# light.net
KiCad netlist of a schematic drawn in EAGLE
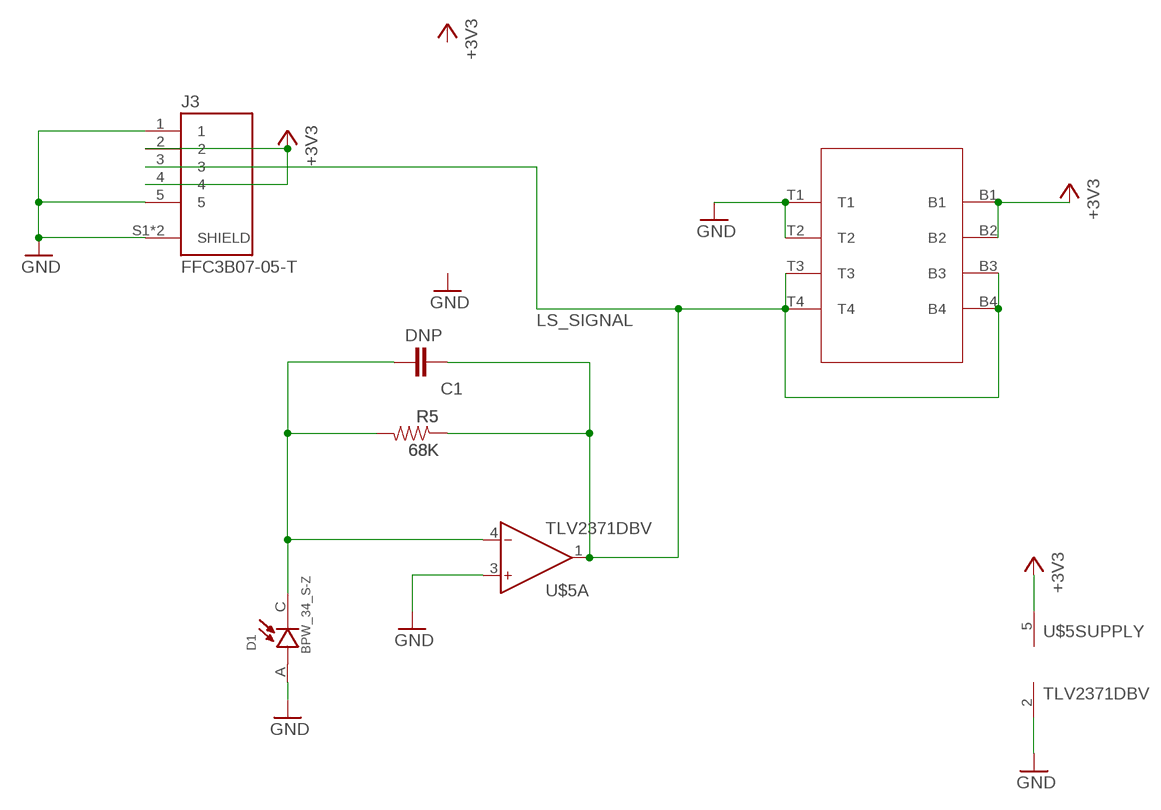
[diagram p0: schematic, sheet 1]

(export (version "E")
  (design (tool "Eeschema 10.0.6"))
  (components
    (comp (ref "C1")
      (value "DNP")
      (footprint "eagle-import:0805")
      (libsource (lib "eagle-import") (part "CAP0805"))
    )
    (comp (ref "D1")
      (value "BPW_34_S-Z")
      (footprint "eagle-import:DIO_BPW_34_S-Z")
      (fields (field (name "MF") "OSRAM Opto") (field (name "MP") "BPW 34 S-Z"))
      (libsource (lib "eagle-import") (part "BPW_34_S-Z"))
    )
    (comp (ref "J3")
      (value "FFC3B07-05-T")
      (footprint "eagle-import:GCT_FFC3B07-05-T")
      (fields (field (name "MF") "Global Connector Technology"))
      (libsource (lib "eagle-import") (part "FFC3B07-05-T"))
    )
    (comp (ref "R5")
      (value "68K")
      (footprint "eagle-import:0805")
      (libsource (lib "eagle-import") (part "RESISTOR0805-RES"))
    )
    (comp (ref "U$1")
      (value "LS_VERT")
      (footprint "eagle-import:LS_VERT")
      (libsource (lib "eagle-import") (part "LS_VERT"))
    )
    (comp (ref "U$5")
      (value "TLV2371DBV")
      (footprint "eagle-import:SOT23-5L")
      (libsource (lib "eagle-import") (part "TLV2371DBV"))
    )
  )
  (nets
    (net (code "1") (name "+3V3") (class "Default")
      (node (ref "J3") (pin "2") (pinfunction "2_2") (pintype "passive"))
      (node (ref "J3") (pin "4") (pinfunction "4_4") (pintype "passive"))
      (node (ref "U$1") (pin "B1") (pinfunction "B1_B1") (pintype "bidirectional"))
      (node (ref "U$1") (pin "B2") (pinfunction "B2_B2") (pintype "bidirectional"))
      (node (ref "U$5") (pin "5") (pinfunction "V+_5") (pintype "power_in"))
    )
    (net (code "2") (name "/LS_SIGNAL") (class "Default")
      (node (ref "C1") (pin "1") (pinfunction "1_1") (pintype "passive"))
      (node (ref "J3") (pin "3") (pinfunction "3_3") (pintype "passive"))
      (node (ref "R5") (pin "1") (pinfunction "1_1") (pintype "passive"))
      (node (ref "U$1") (pin "B3") (pinfunction "B3_B3") (pintype "bidirectional"))
      (node (ref "U$1") (pin "B4") (pinfunction "B4_B4") (pintype "bidirectional"))
      (node (ref "U$1") (pin "T3") (pinfunction "T3_T3") (pintype "bidirectional"))
      (node (ref "U$1") (pin "T4") (pinfunction "T4_T4") (pintype "bidirectional"))
      (node (ref "U$5") (pin "1") (pinfunction "OUT_1") (pintype "output"))
    )
    (net (code "3") (name "GND") (class "Default")
      (node (ref "D1") (pin "A") (pinfunction "A_A") (pintype "passive"))
      (node (ref "J3") (pin "1") (pinfunction "1_1") (pintype "passive"))
      (node (ref "J3") (pin "5") (pinfunction "5_5") (pintype "passive"))
      (node (ref "J3") (pin "S1") (pinfunction "SHIELD_S1") (pintype "passive"))
      (node (ref "J3") (pin "S2") (pinfunction "SHIELD_S2") (pintype "passive"))
      (node (ref "U$1") (pin "T1") (pinfunction "T1_T1") (pintype "bidirectional"))
      (node (ref "U$1") (pin "T2") (pinfunction "T2_T2") (pintype "bidirectional"))
      (node (ref "U$5") (pin "2") (pinfunction "V-_2") (pintype "power_in"))
      (node (ref "U$5") (pin "3") (pinfunction "IN+_3") (pintype "input"))
    )
    (net (code "4") (name "Net-(U$5A-IN-)") (class "Default")
      (node (ref "C1") (pin "2") (pinfunction "2_2") (pintype "passive"))
      (node (ref "D1") (pin "C") (pinfunction "C_C") (pintype "passive"))
      (node (ref "R5") (pin "2") (pinfunction "2_2") (pintype "passive"))
      (node (ref "U$5") (pin "4") (pinfunction "IN-_4") (pintype "input"))
    )
  )
)
